# LightSensor.net
KiCad netlist of a schematic drawn in EAGLE
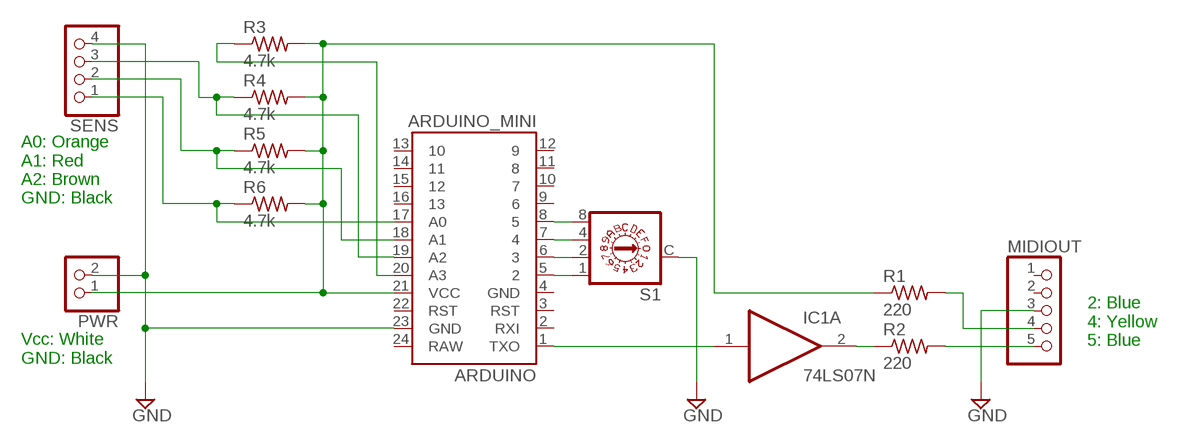
[diagram p0: schematic, sheet 1]

(export (version "E")
  (design (tool "Eeschema 10.0.6"))
  (components
    (comp (ref "ARDUINO")
      (value "ARDUINO_MINI")
      (footprint "eagle-import:ARDUINO_MINI")
      (libsource (lib "eagle-import") (part "ARDUINO_MINI"))
    )
    (comp (ref "IC1")
      (value "74LS07N")
      (footprint "eagle-import:DIL14")
      (libsource (lib "eagle-import") (part "7407NLS"))
    )
    (comp (ref "MIDIOUT")
      (value "PINHD-1X5")
      (footprint "eagle-import:1X05")
      (libsource (lib "eagle-import") (part "PINHD-1X5"))
    )
    (comp (ref "PWR")
      (value "PINHD-1X2")
      (footprint "eagle-import:1X02")
      (libsource (lib "eagle-import") (part "PINHD-1X2"))
    )
    (comp (ref "R1")
      (value "220")
      (footprint "eagle-import:0204_5")
      (libsource (lib "eagle-import") (part "R-US_0204/5"))
    )
    (comp (ref "R2")
      (value "220")
      (footprint "eagle-import:0204_5")
      (libsource (lib "eagle-import") (part "R-US_0204/5"))
    )
    (comp (ref "R3")
      (value "4.7k")
      (footprint "eagle-import:0204_5")
      (libsource (lib "eagle-import") (part "R-US_0204/5"))
    )
    (comp (ref "R4")
      (value "4.7k")
      (footprint "eagle-import:0204_5")
      (libsource (lib "eagle-import") (part "R-US_0204/5"))
    )
    (comp (ref "R5")
      (value "4.7k")
      (footprint "eagle-import:0204_5")
      (libsource (lib "eagle-import") (part "R-US_0204/5"))
    )
    (comp (ref "R6")
      (value "4.7k")
      (footprint "eagle-import:0204_5")
      (libsource (lib "eagle-import") (part "R-US_0204/5"))
    )
    (comp (ref "S1")
      (value "A1353HEX")
      (footprint "eagle-import:A1353HEX")
      (libsource (lib "eagle-import") (part "A1353HEX"))
    )
    (comp (ref "SENS")
      (value "PINHD-1X4")
      (footprint "eagle-import:1X04")
      (libsource (lib "eagle-import") (part "PINHD-1X4"))
    )
  )
  (nets
    (net (code "1") (name "GND") (class "Default")
      (node (ref "ARDUINO") (pin "23") (pinfunction "GND_23") (pintype "bidirectional"))
      (node (ref "MIDIOUT") (pin "3") (pinfunction "3_3") (pintype "passive"))
      (node (ref "PWR") (pin "2") (pinfunction "2_2") (pintype "passive"))
      (node (ref "S1") (pin "C") (pinfunction "C_C") (pintype "passive"))
      (node (ref "SENS") (pin "4") (pinfunction "4_4") (pintype "passive"))
    )
    (net (code "2") (name "Net-(ARDUINO-2)") (class "Default")
      (node (ref "ARDUINO") (pin "5") (pinfunction "2_5") (pintype "bidirectional"))
      (node (ref "S1") (pin "1") (pinfunction "1_1") (pintype "passive"))
    )
    (net (code "3") (name "Net-(ARDUINO-3)") (class "Default")
      (node (ref "ARDUINO") (pin "6") (pinfunction "3_6") (pintype "bidirectional"))
      (node (ref "S1") (pin "2") (pinfunction "2_2") (pintype "passive"))
    )
    (net (code "4") (name "Net-(ARDUINO-4)") (class "Default")
      (node (ref "ARDUINO") (pin "7") (pinfunction "4_7") (pintype "bidirectional"))
      (node (ref "S1") (pin "4") (pinfunction "4_4") (pintype "passive"))
    )
    (net (code "5") (name "Net-(ARDUINO-5)") (class "Default")
      (node (ref "ARDUINO") (pin "8") (pinfunction "5_8") (pintype "bidirectional"))
      (node (ref "S1") (pin "8") (pinfunction "8_8") (pintype "passive"))
    )
    (net (code "6") (name "Net-(ARDUINO-A0)") (class "Default")
      (node (ref "ARDUINO") (pin "17") (pinfunction "A0_17") (pintype "bidirectional"))
      (node (ref "R6") (pin "1") (pinfunction "1_1") (pintype "passive"))
      (node (ref "SENS") (pin "1") (pinfunction "1_1") (pintype "passive"))
    )
    (net (code "7") (name "Net-(ARDUINO-A1)") (class "Default")
      (node (ref "ARDUINO") (pin "18") (pinfunction "A1_18") (pintype "bidirectional"))
      (node (ref "R5") (pin "1") (pinfunction "1_1") (pintype "passive"))
      (node (ref "SENS") (pin "2") (pinfunction "2_2") (pintype "passive"))
    )
    (net (code "8") (name "Net-(ARDUINO-A2)") (class "Default")
      (node (ref "ARDUINO") (pin "19") (pinfunction "A2_19") (pintype "bidirectional"))
      (node (ref "R4") (pin "1") (pinfunction "1_1") (pintype "passive"))
      (node (ref "SENS") (pin "3") (pinfunction "3_3") (pintype "passive"))
    )
    (net (code "9") (name "Net-(ARDUINO-A3)") (class "Default")
      (node (ref "ARDUINO") (pin "20") (pinfunction "A3_20") (pintype "bidirectional"))
      (node (ref "R3") (pin "1") (pinfunction "1_1") (pintype "passive"))
    )
    (net (code "10") (name "Net-(ARDUINO-TXO)") (class "Default")
      (node (ref "ARDUINO") (pin "1") (pinfunction "TXO_1") (pintype "bidirectional"))
      (node (ref "IC1") (pin "1") (pinfunction "I_1") (pintype "input"))
    )
    (net (code "11") (name "Net-(ARDUINO-VCC)") (class "Default")
      (node (ref "ARDUINO") (pin "21") (pinfunction "VCC_21") (pintype "bidirectional"))
      (node (ref "PWR") (pin "1") (pinfunction "1_1") (pintype "passive"))
      (node (ref "R1") (pin "1") (pinfunction "1_1") (pintype "passive"))
      (node (ref "R3") (pin "2") (pinfunction "2_2") (pintype "passive"))
      (node (ref "R4") (pin "2") (pinfunction "2_2") (pintype "passive"))
      (node (ref "R5") (pin "2") (pinfunction "2_2") (pintype "passive"))
      (node (ref "R6") (pin "2") (pinfunction "2_2") (pintype "passive"))
    )
    (net (code "12") (name "Net-(IC1A-O)") (class "Default")
      (node (ref "IC1") (pin "2") (pinfunction "O_2") (pintype "open_collector"))
      (node (ref "R2") (pin "1") (pinfunction "1_1") (pintype "passive"))
    )
    (net (code "13") (name "Net-(MIDIOUT-Pad4)") (class "Default")
      (node (ref "MIDIOUT") (pin "4") (pinfunction "4_4") (pintype "passive"))
      (node (ref "R1") (pin "2") (pinfunction "2_2") (pintype "passive"))
    )
    (net (code "14") (name "Net-(MIDIOUT-Pad5)") (class "Default")
      (node (ref "MIDIOUT") (pin "5") (pinfunction "5_5") (pintype "passive"))
      (node (ref "R2") (pin "2") (pinfunction "2_2") (pintype "passive"))
    )
    (net (code "15") (name "unconnected-(ARDUINO-6-Pad9)") (class "Default")
      (node (ref "ARDUINO") (pin "9") (pinfunction "6_9") (pintype "bidirectional"))
    )
    (net (code "16") (name "unconnected-(ARDUINO-7-Pad10)") (class "Default")
      (node (ref "ARDUINO") (pin "10") (pinfunction "7_10") (pintype "bidirectional"))
    )
    (net (code "17") (name "unconnected-(ARDUINO-8-Pad11)") (class "Default")
      (node (ref "ARDUINO") (pin "11") (pinfunction "8_11") (pintype "bidirectional"))
    )
    (net (code "18") (name "unconnected-(ARDUINO-9-Pad12)") (class "Default")
      (node (ref "ARDUINO") (pin "12") (pinfunction "9_12") (pintype "bidirectional"))
    )
    (net (code "19") (name "unconnected-(ARDUINO-10-Pad13)") (class "Default")
      (node (ref "ARDUINO") (pin "13") (pinfunction "10_13") (pintype "bidirectional"))
    )
    (net (code "20") (name "unconnected-(ARDUINO-11-Pad14)") (class "Default")
      (node (ref "ARDUINO") (pin "14") (pinfunction "11_14") (pintype "bidirectional"))
    )
    (net (code "21") (name "unconnected-(ARDUINO-12-Pad15)") (class "Default")
      (node (ref "ARDUINO") (pin "15") (pinfunction "12_15") (pintype "bidirectional"))
    )
    (net (code "22") (name "unconnected-(ARDUINO-13-Pad16)") (class "Default")
      (node (ref "ARDUINO") (pin "16") (pinfunction "13_16") (pintype "bidirectional"))
    )
    (net (code "23") (name "unconnected-(ARDUINO-GND-Pad4)") (class "Default")
      (node (ref "ARDUINO") (pin "4") (pinfunction "GND_4") (pintype "bidirectional"))
    )
    (net (code "24") (name "unconnected-(ARDUINO-RAW-Pad24)") (class "Default")
      (node (ref "ARDUINO") (pin "24") (pinfunction "RAW_24") (pintype "bidirectional"))
    )
    (net (code "25") (name "unconnected-(ARDUINO-RST-Pad3)") (class "Default")
      (node (ref "ARDUINO") (pin "3") (pinfunction "RST_3") (pintype "bidirectional"))
    )
    (net (code "26") (name "unconnected-(ARDUINO-RST-Pad22)") (class "Default")
      (node (ref "ARDUINO") (pin "22") (pinfunction "RST_22") (pintype "bidirectional"))
    )
    (net (code "27") (name "unconnected-(ARDUINO-RXI-Pad2)") (class "Default")
      (node (ref "ARDUINO") (pin "2") (pinfunction "RXI_2") (pintype "bidirectional"))
    )
    (net (code "28") (name "unconnected-(MIDIOUT-Pad1)") (class "Default")
      (node (ref "MIDIOUT") (pin "1") (pinfunction "1_1") (pintype "passive"))
    )
    (net (code "29") (name "unconnected-(MIDIOUT-Pad2)") (class "Default")
      (node (ref "MIDIOUT") (pin "2") (pinfunction "2_2") (pintype "passive"))
    )
  )
)
